# mini-midi-merge.net
KiCad netlist of a schematic drawn in EAGLE
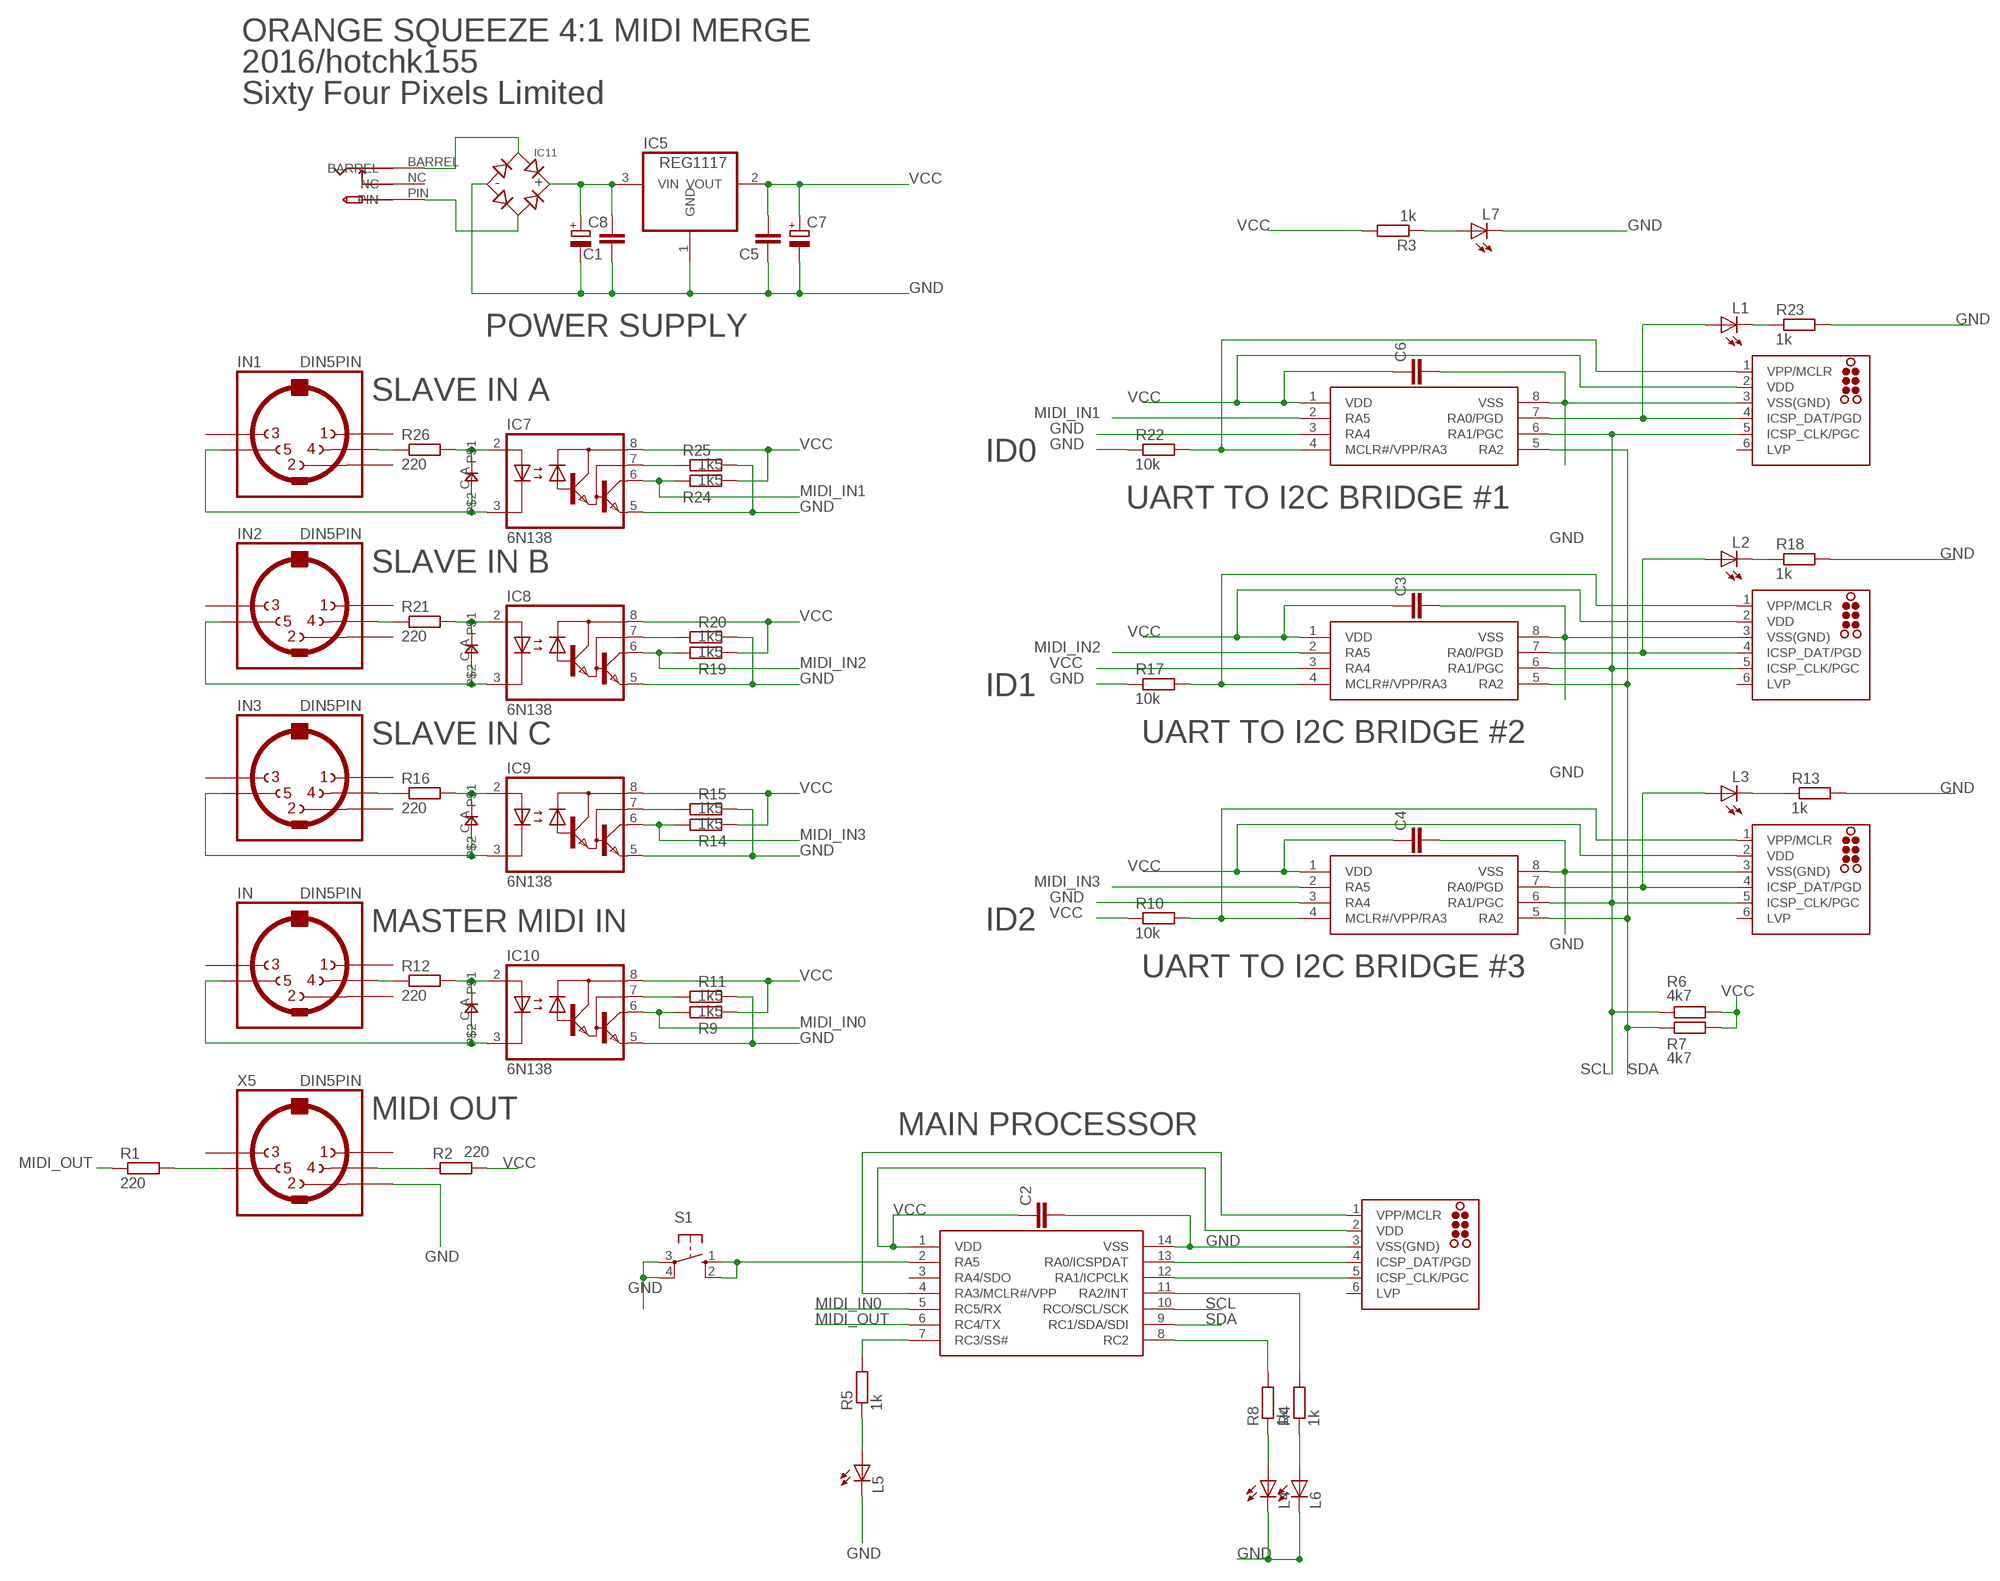
[diagram p0: schematic, sheet 1]

(export (version "E")
  (design (tool "Eeschema 10.0.6"))
  (components
    (comp (ref "C1")
      (value "C-EUC0805")
      (footprint "eagle-import:C0805")
      (libsource (lib "eagle-import") (part "C-EUC0805"))
    )
    (comp (ref "C2")
      (value "C-EUC0805")
      (footprint "eagle-import:C0805")
      (libsource (lib "eagle-import") (part "C-EUC0805"))
    )
    (comp (ref "C3")
      (value "C-EUC0805")
      (footprint "eagle-import:C0805")
      (libsource (lib "eagle-import") (part "C-EUC0805"))
    )
    (comp (ref "C4")
      (value "C-EUC0805")
      (footprint "eagle-import:C0805")
      (libsource (lib "eagle-import") (part "C-EUC0805"))
    )
    (comp (ref "C5")
      (value "C-EUC0805")
      (footprint "eagle-import:C0805")
      (libsource (lib "eagle-import") (part "C-EUC0805"))
    )
    (comp (ref "C6")
      (value "C-EUC0805")
      (footprint "eagle-import:C0805")
      (libsource (lib "eagle-import") (part "C-EUC0805"))
    )
    (comp (ref "C7")
      (value "CPOL-EUE2,5-6E")
      (footprint "eagle-import:E2,5-6E")
      (libsource (lib "eagle-import") (part "CPOL-EUE2,5-6E"))
    )
    (comp (ref "C8")
      (value "CPOL-EUE2,5-6E")
      (footprint "eagle-import:E2,5-6E")
      (libsource (lib "eagle-import") (part "CPOL-EUE2,5-6E"))
    )
    (comp (ref "D1")
      (value "0805DIODE")
      (footprint "eagle-import:0805DIODE")
      (libsource (lib "eagle-import") (part "0805DIODE"))
    )
    (comp (ref "D2")
      (value "0805DIODE")
      (footprint "eagle-import:0805DIODE")
      (libsource (lib "eagle-import") (part "0805DIODE"))
    )
    (comp (ref "D3")
      (value "0805DIODE")
      (footprint "eagle-import:0805DIODE")
      (libsource (lib "eagle-import") (part "0805DIODE"))
    )
    (comp (ref "D4")
      (value "0805DIODE")
      (footprint "eagle-import:0805DIODE")
      (libsource (lib "eagle-import") (part "0805DIODE"))
    )
    (comp (ref "IC1")
      (value "PIC16F1825SO14")
      (footprint "eagle-import:SO14")
      (libsource (lib "eagle-import") (part "PIC16F1825SO14"))
    )
    (comp (ref "IC2")
      (value "PIC12F1822SO08")
      (footprint "eagle-import:SO08")
      (libsource (lib "eagle-import") (part "PIC12F1822SO08"))
    )
    (comp (ref "IC3")
      (value "PIC12F1822SO08")
      (footprint "eagle-import:SO08")
      (libsource (lib "eagle-import") (part "PIC12F1822SO08"))
    )
    (comp (ref "IC4")
      (value "PIC12F1822SO08")
      (footprint "eagle-import:SO08")
      (libsource (lib "eagle-import") (part "PIC12F1822SO08"))
    )
    (comp (ref "IC5")
      (value "REG1117")
      (footprint "eagle-import:SOT223")
      (libsource (lib "eagle-import") (part "REG1117"))
    )
    (comp (ref "IC7")
      (value "6N138")
      (footprint "eagle-import:DIL08")
      (fields (field (name "MF") "VISHAY/TELEFUNKEN"))
      (libsource (lib "eagle-import") (part "6N138"))
    )
    (comp (ref "IC8")
      (value "6N138")
      (footprint "eagle-import:DIL08")
      (fields (field (name "MF") "VISHAY/TELEFUNKEN"))
      (libsource (lib "eagle-import") (part "6N138"))
    )
    (comp (ref "IC9")
      (value "6N138")
      (footprint "eagle-import:DIL08")
      (fields (field (name "MF") "VISHAY/TELEFUNKEN"))
      (libsource (lib "eagle-import") (part "6N138"))
    )
    (comp (ref "IC10")
      (value "6N138")
      (footprint "eagle-import:DIL08")
      (fields (field (name "MF") "VISHAY/TELEFUNKEN"))
      (libsource (lib "eagle-import") (part "6N138"))
    )
    (comp (ref "IC11")
      (value "BRIDGERECTIFIER")
      (footprint "eagle-import:SOIC-4")
      (libsource (lib "eagle-import") (part "BRIDGERECTIFIER"))
    )
    (comp (ref "ICSP1")
      (value "TC2030-MCP-NL")
      (footprint "eagle-import:TC2030-MCP-NL")
      (libsource (lib "eagle-import") (part "TC2030-MCP-NL"))
    )
    (comp (ref "ICSP2")
      (value "TC2030-MCP-NL")
      (footprint "eagle-import:TC2030-MCP-NL")
      (libsource (lib "eagle-import") (part "TC2030-MCP-NL"))
    )
    (comp (ref "ICSP3")
      (value "TC2030-MCP-NL")
      (footprint "eagle-import:TC2030-MCP-NL")
      (libsource (lib "eagle-import") (part "TC2030-MCP-NL"))
    )
    (comp (ref "ICSP4")
      (value "TC2030-MCP-NL")
      (footprint "eagle-import:TC2030-MCP-NL")
      (libsource (lib "eagle-import") (part "TC2030-MCP-NL"))
    )
    (comp (ref "IN")
      (value "DIN5PIN")
      (footprint "eagle-import:EDGEDIN")
      (libsource (lib "eagle-import") (part "DIN5PIN"))
    )
    (comp (ref "IN1")
      (value "DIN5PIN")
      (footprint "eagle-import:EDGEDIN")
      (libsource (lib "eagle-import") (part "DIN5PIN"))
    )
    (comp (ref "IN2")
      (value "DIN5PIN")
      (footprint "eagle-import:EDGEDIN")
      (libsource (lib "eagle-import") (part "DIN5PIN"))
    )
    (comp (ref "IN3")
      (value "DIN5PIN")
      (footprint "eagle-import:EDGEDIN")
      (libsource (lib "eagle-import") (part "DIN5PIN"))
    )
    (comp (ref "L1")
      (value "LED3MM")
      (footprint "eagle-import:LED3MM")
      (libsource (lib "eagle-import") (part "LED3MM"))
    )
    (comp (ref "L2")
      (value "LED3MM")
      (footprint "eagle-import:LED3MM")
      (libsource (lib "eagle-import") (part "LED3MM"))
    )
    (comp (ref "L3")
      (value "LED3MM")
      (footprint "eagle-import:LED3MM")
      (libsource (lib "eagle-import") (part "LED3MM"))
    )
    (comp (ref "L4")
      (value "LED3MM")
      (footprint "eagle-import:LED3MM")
      (libsource (lib "eagle-import") (part "LED3MM"))
    )
    (comp (ref "L5")
      (value "LED3MM")
      (footprint "eagle-import:LED3MM")
      (libsource (lib "eagle-import") (part "LED3MM"))
    )
    (comp (ref "L6")
      (value "LED3MM")
      (footprint "eagle-import:LED3MM")
      (libsource (lib "eagle-import") (part "LED3MM"))
    )
    (comp (ref "L7")
      (value "LED3MM")
      (footprint "eagle-import:LED3MM")
      (libsource (lib "eagle-import") (part "LED3MM"))
    )
    (comp (ref "R1")
      (value "220")
      (footprint "eagle-import:R0805")
      (libsource (lib "eagle-import") (part "R-EU_R0805"))
    )
    (comp (ref "R2")
      (value "220")
      (footprint "eagle-import:R0805")
      (libsource (lib "eagle-import") (part "R-EU_R0805"))
    )
    (comp (ref "R3")
      (value "1k")
      (footprint "eagle-import:R0805")
      (libsource (lib "eagle-import") (part "R-EU_R0805"))
    )
    (comp (ref "R4")
      (value "1k")
      (footprint "eagle-import:R0805")
      (libsource (lib "eagle-import") (part "R-EU_R0805"))
    )
    (comp (ref "R5")
      (value "1k")
      (footprint "eagle-import:R0805")
      (libsource (lib "eagle-import") (part "R-EU_R0805"))
    )
    (comp (ref "R6")
      (value "4k7")
      (footprint "eagle-import:R0805")
      (libsource (lib "eagle-import") (part "R-EU_R0805"))
    )
    (comp (ref "R7")
      (value "4k7")
      (footprint "eagle-import:R0805")
      (libsource (lib "eagle-import") (part "R-EU_R0805"))
    )
    (comp (ref "R8")
      (value "1k")
      (footprint "eagle-import:R0805")
      (libsource (lib "eagle-import") (part "R-EU_R0805"))
    )
    (comp (ref "R9")
      (value "1k5")
      (footprint "eagle-import:R0805")
      (libsource (lib "eagle-import") (part "R-EU_R0805"))
    )
    (comp (ref "R10")
      (value "10k")
      (footprint "eagle-import:R0805")
      (libsource (lib "eagle-import") (part "R-EU_R0805"))
    )
    (comp (ref "R11")
      (value "1k5")
      (footprint "eagle-import:R0805")
      (libsource (lib "eagle-import") (part "R-EU_R0805"))
    )
    (comp (ref "R12")
      (value "220")
      (footprint "eagle-import:R0805")
      (libsource (lib "eagle-import") (part "R-EU_R0805"))
    )
    (comp (ref "R13")
      (value "1k")
      (footprint "eagle-import:R0805")
      (libsource (lib "eagle-import") (part "R-EU_R0805"))
    )
    (comp (ref "R14")
      (value "1k5")
      (footprint "eagle-import:R0805")
      (libsource (lib "eagle-import") (part "R-EU_R0805"))
    )
    (comp (ref "R15")
      (value "1k5")
      (footprint "eagle-import:R0805")
      (libsource (lib "eagle-import") (part "R-EU_R0805"))
    )
    (comp (ref "R16")
      (value "220")
      (footprint "eagle-import:R0805")
      (libsource (lib "eagle-import") (part "R-EU_R0805"))
    )
    (comp (ref "R17")
      (value "10k")
      (footprint "eagle-import:R0805")
      (libsource (lib "eagle-import") (part "R-EU_R0805"))
    )
    (comp (ref "R18")
      (value "1k")
      (footprint "eagle-import:R0805")
      (libsource (lib "eagle-import") (part "R-EU_R0805"))
    )
    (comp (ref "R19")
      (value "1k5")
      (footprint "eagle-import:R0805")
      (libsource (lib "eagle-import") (part "R-EU_R0805"))
    )
    (comp (ref "R20")
      (value "1k5")
      (footprint "eagle-import:R0805")
      (libsource (lib "eagle-import") (part "R-EU_R0805"))
    )
    (comp (ref "R21")
      (value "220")
      (footprint "eagle-import:R0805")
      (libsource (lib "eagle-import") (part "R-EU_R0805"))
    )
    (comp (ref "R22")
      (value "10k")
      (footprint "eagle-import:R0805")
      (libsource (lib "eagle-import") (part "R-EU_R0805"))
    )
    (comp (ref "R23")
      (value "1k")
      (footprint "eagle-import:R0805")
      (libsource (lib "eagle-import") (part "R-EU_R0805"))
    )
    (comp (ref "R24")
      (value "1k5")
      (footprint "eagle-import:R0805")
      (libsource (lib "eagle-import") (part "R-EU_R0805"))
    )
    (comp (ref "R25")
      (value "1k5")
      (footprint "eagle-import:R0805")
      (libsource (lib "eagle-import") (part "R-EU_R0805"))
    )
    (comp (ref "R26")
      (value "220")
      (footprint "eagle-import:R0805")
      (libsource (lib "eagle-import") (part "R-EU_R0805"))
    )
    (comp (ref "S1")
      (value "10-XX")
      (footprint "eagle-import:B3F-10XX")
      (fields (field (name "MPN") "B3F-1000"))
      (libsource (lib "eagle-import") (part "10-XX"))
    )
    (comp (ref "U$9")
      (value "PWR_SOCKET_2_1MM")
      (footprint "eagle-import:PWR_SOCKET_2_1MM")
      (libsource (lib "eagle-import") (part "PWR_SOCKET_2_1MM"))
    )
    (comp (ref "X5")
      (value "DIN5PIN")
      (footprint "eagle-import:EDGEDIN")
      (libsource (lib "eagle-import") (part "DIN5PIN"))
    )
  )
  (nets
    (net (code "1") (name "/GND") (class "Default")
      (node (ref "C1") (pin "1") (pinfunction "1_1") (pintype "passive"))
      (node (ref "C2") (pin "2") (pinfunction "2_2") (pintype "passive"))
      (node (ref "C3") (pin "2") (pinfunction "2_2") (pintype "passive"))
      (node (ref "C4") (pin "2") (pinfunction "2_2") (pintype "passive"))
      (node (ref "C5") (pin "1") (pinfunction "1_1") (pintype "passive"))
      (node (ref "C6") (pin "2") (pinfunction "2_2") (pintype "passive"))
      (node (ref "C7") (pin "-") (pinfunction "-_-") (pintype "passive"))
      (node (ref "C8") (pin "-") (pinfunction "-_-") (pintype "passive"))
      (node (ref "IC1") (pin "14") (pinfunction "VSS_14") (pintype "power_in"))
      (node (ref "IC10") (pin "5") (pinfunction "GND_5") (pintype "passive"))
      (node (ref "IC11") (pin "-") (pinfunction "-_-") (pintype "passive"))
      (node (ref "IC2") (pin "3") (pinfunction "RA4_3") (pintype "bidirectional"))
      (node (ref "IC2") (pin "8") (pinfunction "VSS_8") (pintype "power_in"))
      (node (ref "IC3") (pin "8") (pinfunction "VSS_8") (pintype "power_in"))
      (node (ref "IC4") (pin "3") (pinfunction "RA4_3") (pintype "bidirectional"))
      (node (ref "IC4") (pin "8") (pinfunction "VSS_8") (pintype "power_in"))
      (node (ref "IC5") (pin "1") (pinfunction "GND_1") (pintype "power_in"))
      (node (ref "IC7") (pin "5") (pinfunction "GND_5") (pintype "passive"))
      (node (ref "IC8") (pin "5") (pinfunction "GND_5") (pintype "passive"))
      (node (ref "IC9") (pin "5") (pinfunction "GND_5") (pintype "passive"))
      (node (ref "ICSP1") (pin "3") (pinfunction "VSS(GND)_3") (pintype "power_in"))
      (node (ref "ICSP2") (pin "3") (pinfunction "VSS(GND)_3") (pintype "power_in"))
      (node (ref "ICSP3") (pin "3") (pinfunction "VSS(GND)_3") (pintype "power_in"))
      (node (ref "ICSP4") (pin "3") (pinfunction "VSS(GND)_3") (pintype "power_in"))
      (node (ref "L4") (pin "K") (pinfunction "C_K") (pintype "passive"))
      (node (ref "L5") (pin "K") (pinfunction "C_K") (pintype "passive"))
      (node (ref "L6") (pin "K") (pinfunction "C_K") (pintype "passive"))
      (node (ref "L7") (pin "K") (pinfunction "C_K") (pintype "passive"))
      (node (ref "R11") (pin "2") (pinfunction "2_2") (pintype "passive"))
      (node (ref "R13") (pin "2") (pinfunction "2_2") (pintype "passive"))
      (node (ref "R15") (pin "2") (pinfunction "2_2") (pintype "passive"))
      (node (ref "R17") (pin "1") (pinfunction "1_1") (pintype "passive"))
      (node (ref "R18") (pin "2") (pinfunction "2_2") (pintype "passive"))
      (node (ref "R20") (pin "2") (pinfunction "2_2") (pintype "passive"))
      (node (ref "R22") (pin "1") (pinfunction "1_1") (pintype "passive"))
      (node (ref "R23") (pin "2") (pinfunction "2_2") (pintype "passive"))
      (node (ref "R25") (pin "2") (pinfunction "2_2") (pintype "passive"))
      (node (ref "S1") (pin "3") (pinfunction "P_3") (pintype "passive"))
      (node (ref "S1") (pin "4") (pinfunction "P1_4") (pintype "passive"))
      (node (ref "X5") (pin "2") (pinfunction "2_2") (pintype "passive"))
    )
    (net (code "2") (name "/MIDI_IN0") (class "Default")
      (node (ref "IC1") (pin "5") (pinfunction "RC5/RX_5") (pintype "bidirectional"))
      (node (ref "IC10") (pin "6") (pinfunction "VO_6") (pintype "passive"))
      (node (ref "R9") (pin "1") (pinfunction "1_1") (pintype "passive"))
    )
    (net (code "3") (name "/MIDI_IN1") (class "Default")
      (node (ref "IC4") (pin "2") (pinfunction "RA5_2") (pintype "bidirectional"))
      (node (ref "IC7") (pin "6") (pinfunction "VO_6") (pintype "passive"))
      (node (ref "R24") (pin "1") (pinfunction "1_1") (pintype "passive"))
    )
    (net (code "4") (name "/MIDI_IN2") (class "Default")
      (node (ref "IC3") (pin "2") (pinfunction "RA5_2") (pintype "bidirectional"))
      (node (ref "IC8") (pin "6") (pinfunction "VO_6") (pintype "passive"))
      (node (ref "R19") (pin "1") (pinfunction "1_1") (pintype "passive"))
    )
    (net (code "5") (name "/MIDI_IN3") (class "Default")
      (node (ref "IC2") (pin "2") (pinfunction "RA5_2") (pintype "bidirectional"))
      (node (ref "IC9") (pin "6") (pinfunction "VO_6") (pintype "passive"))
      (node (ref "R14") (pin "1") (pinfunction "1_1") (pintype "passive"))
    )
    (net (code "6") (name "/MIDI_OUT") (class "Default")
      (node (ref "IC1") (pin "6") (pinfunction "RC4/TX_6") (pintype "bidirectional"))
      (node (ref "R1") (pin "1") (pinfunction "1_1") (pintype "passive"))
    )
    (net (code "7") (name "/SCL") (class "Default")
      (node (ref "IC1") (pin "10") (pinfunction "RCO/SCL/SCK_10") (pintype "bidirectional"))
      (node (ref "IC2") (pin "6") (pinfunction "RA1/PGC_6") (pintype "bidirectional"))
      (node (ref "IC3") (pin "6") (pinfunction "RA1/PGC_6") (pintype "bidirectional"))
      (node (ref "IC4") (pin "6") (pinfunction "RA1/PGC_6") (pintype "bidirectional"))
      (node (ref "ICSP2") (pin "5") (pinfunction "ICSP_CLK/PGC_5") (pintype "output"))
      (node (ref "ICSP3") (pin "5") (pinfunction "ICSP_CLK/PGC_5") (pintype "output"))
      (node (ref "ICSP4") (pin "5") (pinfunction "ICSP_CLK/PGC_5") (pintype "output"))
      (node (ref "R6") (pin "1") (pinfunction "1_1") (pintype "passive"))
    )
    (net (code "8") (name "/SDA") (class "Default")
      (node (ref "IC1") (pin "9") (pinfunction "RC1/SDA/SDI_9") (pintype "bidirectional"))
      (node (ref "IC2") (pin "5") (pinfunction "RA2_5") (pintype "bidirectional"))
      (node (ref "IC3") (pin "5") (pinfunction "RA2_5") (pintype "bidirectional"))
      (node (ref "IC4") (pin "5") (pinfunction "RA2_5") (pintype "bidirectional"))
      (node (ref "R7") (pin "1") (pinfunction "1_1") (pintype "passive"))
    )
    (net (code "9") (name "/VCC") (class "Default")
      (node (ref "C2") (pin "1") (pinfunction "1_1") (pintype "passive"))
      (node (ref "C3") (pin "1") (pinfunction "1_1") (pintype "passive"))
      (node (ref "C4") (pin "1") (pinfunction "1_1") (pintype "passive"))
      (node (ref "C5") (pin "2") (pinfunction "2_2") (pintype "passive"))
      (node (ref "C6") (pin "1") (pinfunction "1_1") (pintype "passive"))
      (node (ref "C7") (pin "+") (pinfunction "+_+") (pintype "passive"))
      (node (ref "IC1") (pin "1") (pinfunction "VDD_1") (pintype "power_in"))
      (node (ref "IC10") (pin "8") (pinfunction "VCC_8") (pintype "passive"))
      (node (ref "IC2") (pin "1") (pinfunction "VDD_1") (pintype "power_in"))
      (node (ref "IC3") (pin "1") (pinfunction "VDD_1") (pintype "power_in"))
      (node (ref "IC3") (pin "3") (pinfunction "RA4_3") (pintype "bidirectional"))
      (node (ref "IC4") (pin "1") (pinfunction "VDD_1") (pintype "power_in"))
      (node (ref "IC5") (pin "2") (pinfunction "VOUT_2") (pintype "output"))
      (node (ref "IC7") (pin "8") (pinfunction "VCC_8") (pintype "passive"))
      (node (ref "IC8") (pin "8") (pinfunction "VCC_8") (pintype "passive"))
      (node (ref "IC9") (pin "8") (pinfunction "VCC_8") (pintype "passive"))
      (node (ref "ICSP1") (pin "2") (pinfunction "VDD_2") (pintype "power_in"))
      (node (ref "ICSP2") (pin "2") (pinfunction "VDD_2") (pintype "power_in"))
      (node (ref "ICSP3") (pin "2") (pinfunction "VDD_2") (pintype "power_in"))
      (node (ref "ICSP4") (pin "2") (pinfunction "VDD_2") (pintype "power_in"))
      (node (ref "R10") (pin "1") (pinfunction "1_1") (pintype "passive"))
      (node (ref "R14") (pin "2") (pinfunction "2_2") (pintype "passive"))
      (node (ref "R19") (pin "2") (pinfunction "2_2") (pintype "passive"))
      (node (ref "R2") (pin "2") (pinfunction "2_2") (pintype "passive"))
      (node (ref "R24") (pin "2") (pinfunction "2_2") (pintype "passive"))
      (node (ref "R3") (pin "2") (pinfunction "2_2") (pintype "passive"))
      (node (ref "R6") (pin "2") (pinfunction "2_2") (pintype "passive"))
      (node (ref "R7") (pin "2") (pinfunction "2_2") (pintype "passive"))
      (node (ref "R9") (pin "2") (pinfunction "2_2") (pintype "passive"))
    )
    (net (code "10") (name "Net-(D1-P$1)") (class "Default")
      (node (ref "D1") (pin "C") (pinfunction "P$1_C") (pintype "bidirectional"))
      (node (ref "IC10") (pin "3") (pinfunction "C_3") (pintype "passive"))
      (node (ref "IN") (pin "5") (pinfunction "5_5") (pintype "passive"))
    )
    (net (code "11") (name "Net-(D1-P$2)") (class "Default")
      (node (ref "D1") (pin "A") (pinfunction "P$2_A") (pintype "bidirectional"))
      (node (ref "IC10") (pin "2") (pinfunction "A_2") (pintype "passive"))
      (node (ref "R12") (pin "2") (pinfunction "2_2") (pintype "passive"))
    )
    (net (code "12") (name "Net-(D2-P$1)") (class "Default")
      (node (ref "D2") (pin "C") (pinfunction "P$1_C") (pintype "bidirectional"))
      (node (ref "IC9") (pin "3") (pinfunction "C_3") (pintype "passive"))
      (node (ref "IN3") (pin "5") (pinfunction "5_5") (pintype "passive"))
    )
    (net (code "13") (name "Net-(D2-P$2)") (class "Default")
      (node (ref "D2") (pin "A") (pinfunction "P$2_A") (pintype "bidirectional"))
      (node (ref "IC9") (pin "2") (pinfunction "A_2") (pintype "passive"))
      (node (ref "R16") (pin "2") (pinfunction "2_2") (pintype "passive"))
    )
    (net (code "14") (name "Net-(D3-P$1)") (class "Default")
      (node (ref "D3") (pin "C") (pinfunction "P$1_C") (pintype "bidirectional"))
      (node (ref "IC8") (pin "3") (pinfunction "C_3") (pintype "passive"))
      (node (ref "IN2") (pin "5") (pinfunction "5_5") (pintype "passive"))
    )
    (net (code "15") (name "Net-(D3-P$2)") (class "Default")
      (node (ref "D3") (pin "A") (pinfunction "P$2_A") (pintype "bidirectional"))
      (node (ref "IC8") (pin "2") (pinfunction "A_2") (pintype "passive"))
      (node (ref "R21") (pin "2") (pinfunction "2_2") (pintype "passive"))
    )
    (net (code "16") (name "Net-(D4-P$1)") (class "Default")
      (node (ref "D4") (pin "C") (pinfunction "P$1_C") (pintype "bidirectional"))
      (node (ref "IC7") (pin "3") (pinfunction "C_3") (pintype "passive"))
      (node (ref "IN1") (pin "5") (pinfunction "5_5") (pintype "passive"))
    )
    (net (code "17") (name "Net-(D4-P$2)") (class "Default")
      (node (ref "D4") (pin "A") (pinfunction "P$2_A") (pintype "bidirectional"))
      (node (ref "IC7") (pin "2") (pinfunction "A_2") (pintype "passive"))
      (node (ref "R26") (pin "2") (pinfunction "2_2") (pintype "passive"))
    )
    (net (code "18") (name "Net-(IC1-RA0{slash}ICSPDAT)") (class "Default")
      (node (ref "IC1") (pin "13") (pinfunction "RA0/ICSPDAT_13") (pintype "bidirectional"))
      (node (ref "ICSP1") (pin "4") (pinfunction "ICSP_DAT/PGD_4") (pintype "bidirectional"))
    )
    (net (code "19") (name "Net-(IC1-RA1{slash}ICPCLK)") (class "Default")
      (node (ref "IC1") (pin "12") (pinfunction "RA1/ICPCLK_12") (pintype "bidirectional"))
      (node (ref "ICSP1") (pin "5") (pinfunction "ICSP_CLK/PGC_5") (pintype "output"))
    )
    (net (code "20") (name "Net-(IC1-RA2{slash}INT)") (class "Default")
      (node (ref "IC1") (pin "11") (pinfunction "RA2/INT_11") (pintype "bidirectional"))
      (node (ref "R4") (pin "2") (pinfunction "2_2") (pintype "passive"))
    )
    (net (code "21") (name "Net-(IC1-RA3{slash}MCLR#{slash}VPP)") (class "Default")
      (node (ref "IC1") (pin "4") (pinfunction "RA3/MCLR#/VPP_4") (pintype "input"))
      (node (ref "ICSP1") (pin "1") (pinfunction "VPP/MCLR_1") (pintype "passive"))
    )
    (net (code "22") (name "Net-(IC1-RA5)") (class "Default")
      (node (ref "IC1") (pin "2") (pinfunction "RA5_2") (pintype "bidirectional"))
      (node (ref "S1") (pin "1") (pinfunction "S_1") (pintype "passive"))
      (node (ref "S1") (pin "2") (pinfunction "S1_2") (pintype "passive"))
    )
    (net (code "23") (name "Net-(IC1-RC2)") (class "Default")
      (node (ref "IC1") (pin "8") (pinfunction "RC2_8") (pintype "bidirectional"))
      (node (ref "R8") (pin "2") (pinfunction "2_2") (pintype "passive"))
    )
    (net (code "24") (name "Net-(IC1-RC3{slash}SS#)") (class "Default")
      (node (ref "IC1") (pin "7") (pinfunction "RC3/SS#_7") (pintype "bidirectional"))
      (node (ref "R5") (pin "2") (pinfunction "2_2") (pintype "passive"))
    )
    (net (code "25") (name "Net-(IC2-MCLR#{slash}VPP{slash}RA3)") (class "Default")
      (node (ref "IC2") (pin "4") (pinfunction "MCLR#/VPP/RA3_4") (pintype "bidirectional"))
      (node (ref "ICSP2") (pin "1") (pinfunction "VPP/MCLR_1") (pintype "passive"))
      (node (ref "R10") (pin "2") (pinfunction "2_2") (pintype "passive"))
    )
    (net (code "26") (name "Net-(IC2-RA0{slash}PGD)") (class "Default")
      (node (ref "IC2") (pin "7") (pinfunction "RA0/PGD_7") (pintype "bidirectional"))
      (node (ref "ICSP2") (pin "4") (pinfunction "ICSP_DAT/PGD_4") (pintype "bidirectional"))
      (node (ref "L3") (pin "A") (pinfunction "A_A") (pintype "passive"))
    )
    (net (code "27") (name "Net-(IC3-MCLR#{slash}VPP{slash}RA3)") (class "Default")
      (node (ref "IC3") (pin "4") (pinfunction "MCLR#/VPP/RA3_4") (pintype "bidirectional"))
      (node (ref "ICSP3") (pin "1") (pinfunction "VPP/MCLR_1") (pintype "passive"))
      (node (ref "R17") (pin "2") (pinfunction "2_2") (pintype "passive"))
    )
    (net (code "28") (name "Net-(IC3-RA0{slash}PGD)") (class "Default")
      (node (ref "IC3") (pin "7") (pinfunction "RA0/PGD_7") (pintype "bidirectional"))
      (node (ref "ICSP3") (pin "4") (pinfunction "ICSP_DAT/PGD_4") (pintype "bidirectional"))
      (node (ref "L2") (pin "A") (pinfunction "A_A") (pintype "passive"))
    )
    (net (code "29") (name "Net-(IC4-MCLR#{slash}VPP{slash}RA3)") (class "Default")
      (node (ref "IC4") (pin "4") (pinfunction "MCLR#/VPP/RA3_4") (pintype "bidirectional"))
      (node (ref "ICSP4") (pin "1") (pinfunction "VPP/MCLR_1") (pintype "passive"))
      (node (ref "R22") (pin "2") (pinfunction "2_2") (pintype "passive"))
    )
    (net (code "30") (name "Net-(IC4-RA0{slash}PGD)") (class "Default")
      (node (ref "IC4") (pin "7") (pinfunction "RA0/PGD_7") (pintype "bidirectional"))
      (node (ref "ICSP4") (pin "4") (pinfunction "ICSP_DAT/PGD_4") (pintype "bidirectional"))
      (node (ref "L1") (pin "A") (pinfunction "A_A") (pintype "passive"))
    )
    (net (code "31") (name "Net-(IC5-VIN)") (class "Default")
      (node (ref "C1") (pin "2") (pinfunction "2_2") (pintype "passive"))
      (node (ref "C8") (pin "+") (pinfunction "+_+") (pintype "passive"))
      (node (ref "IC11") (pin "+") (pinfunction "+_+") (pintype "passive"))
      (node (ref "IC5") (pin "3") (pinfunction "VIN_3") (pintype "input"))
    )
    (net (code "32") (name "Net-(IC7-VB)") (class "Default")
      (node (ref "IC7") (pin "7") (pinfunction "VB_7") (pintype "passive"))
      (node (ref "R25") (pin "1") (pinfunction "1_1") (pintype "passive"))
    )
    (net (code "33") (name "Net-(IC8-VB)") (class "Default")
      (node (ref "IC8") (pin "7") (pinfunction "VB_7") (pintype "passive"))
      (node (ref "R20") (pin "1") (pinfunction "1_1") (pintype "passive"))
    )
    (net (code "34") (name "Net-(IC9-VB)") (class "Default")
      (node (ref "IC9") (pin "7") (pinfunction "VB_7") (pintype "passive"))
      (node (ref "R15") (pin "1") (pinfunction "1_1") (pintype "passive"))
    )
    (net (code "35") (name "Net-(IC10-VB)") (class "Default")
      (node (ref "IC10") (pin "7") (pinfunction "VB_7") (pintype "passive"))
      (node (ref "R11") (pin "1") (pinfunction "1_1") (pintype "passive"))
    )
    (net (code "36") (name "Net-(IC11-AC1)") (class "Default")
      (node (ref "IC11") (pin "~1") (pinfunction "AC1_~1") (pintype "passive"))
      (node (ref "U$9") (pin "BARREL") (pinfunction "BARREL_BARREL") (pintype "bidirectional"))
    )
    (net (code "37") (name "Net-(IC11-AC2)") (class "Default")
      (node (ref "IC11") (pin "~2") (pinfunction "AC2_~2") (pintype "passive"))
      (node (ref "U$9") (pin "PIN") (pinfunction "PIN_PIN") (pintype "bidirectional"))
    )
    (net (code "38") (name "Net-(IN-Pad4)") (class "Default")
      (node (ref "IN") (pin "4") (pinfunction "4_4") (pintype "passive"))
      (node (ref "R12") (pin "1") (pinfunction "1_1") (pintype "passive"))
    )
    (net (code "39") (name "Net-(IN1-Pad4)") (class "Default")
      (node (ref "IN1") (pin "4") (pinfunction "4_4") (pintype "passive"))
      (node (ref "R26") (pin "1") (pinfunction "1_1") (pintype "passive"))
    )
    (net (code "40") (name "Net-(IN2-Pad4)") (class "Default")
      (node (ref "IN2") (pin "4") (pinfunction "4_4") (pintype "passive"))
      (node (ref "R21") (pin "1") (pinfunction "1_1") (pintype "passive"))
    )
    (net (code "41") (name "Net-(IN3-Pad4)") (class "Default")
      (node (ref "IN3") (pin "4") (pinfunction "4_4") (pintype "passive"))
      (node (ref "R16") (pin "1") (pinfunction "1_1") (pintype "passive"))
    )
    (net (code "42") (name "Net-(L1-C)") (class "Default")
      (node (ref "L1") (pin "K") (pinfunction "C_K") (pintype "passive"))
      (node (ref "R23") (pin "1") (pinfunction "1_1") (pintype "passive"))
    )
    (net (code "43") (name "Net-(L2-C)") (class "Default")
      (node (ref "L2") (pin "K") (pinfunction "C_K") (pintype "passive"))
      (node (ref "R18") (pin "1") (pinfunction "1_1") (pintype "passive"))
    )
    (net (code "44") (name "Net-(L3-C)") (class "Default")
      (node (ref "L3") (pin "K") (pinfunction "C_K") (pintype "passive"))
      (node (ref "R13") (pin "1") (pinfunction "1_1") (pintype "passive"))
    )
    (net (code "45") (name "Net-(L4-PadA)") (class "Default")
      (node (ref "L4") (pin "A") (pinfunction "A_A") (pintype "passive"))
      (node (ref "R8") (pin "1") (pinfunction "1_1") (pintype "passive"))
    )
    (net (code "46") (name "Net-(L5-PadA)") (class "Default")
      (node (ref "L5") (pin "A") (pinfunction "A_A") (pintype "passive"))
      (node (ref "R5") (pin "1") (pinfunction "1_1") (pintype "passive"))
    )
    (net (code "47") (name "Net-(L6-PadA)") (class "Default")
      (node (ref "L6") (pin "A") (pinfunction "A_A") (pintype "passive"))
      (node (ref "R4") (pin "1") (pinfunction "1_1") (pintype "passive"))
    )
    (net (code "48") (name "Net-(L7-PadA)") (class "Default")
      (node (ref "L7") (pin "A") (pinfunction "A_A") (pintype "passive"))
      (node (ref "R3") (pin "1") (pinfunction "1_1") (pintype "passive"))
    )
    (net (code "49") (name "Net-(R1-Pad2)") (class "Default")
      (node (ref "R1") (pin "2") (pinfunction "2_2") (pintype "passive"))
      (node (ref "X5") (pin "5") (pinfunction "5_5") (pintype "passive"))
    )
    (net (code "50") (name "Net-(R2-Pad1)") (class "Default")
      (node (ref "R2") (pin "1") (pinfunction "1_1") (pintype "passive"))
      (node (ref "X5") (pin "4") (pinfunction "4_4") (pintype "passive"))
    )
    (net (code "51") (name "unconnected-(IC1-RA4{slash}SDO-Pad3)") (class "Default")
      (node (ref "IC1") (pin "3") (pinfunction "RA4/SDO_3") (pintype "bidirectional"))
    )
    (net (code "52") (name "unconnected-(ICSP1-LVP-Pad6)") (class "Default")
      (node (ref "ICSP1") (pin "6") (pinfunction "LVP_6") (pintype "bidirectional"))
    )
    (net (code "53") (name "unconnected-(ICSP2-LVP-Pad6)") (class "Default")
      (node (ref "ICSP2") (pin "6") (pinfunction "LVP_6") (pintype "bidirectional"))
    )
    (net (code "54") (name "unconnected-(ICSP3-LVP-Pad6)") (class "Default")
      (node (ref "ICSP3") (pin "6") (pinfunction "LVP_6") (pintype "bidirectional"))
    )
    (net (code "55") (name "unconnected-(ICSP4-LVP-Pad6)") (class "Default")
      (node (ref "ICSP4") (pin "6") (pinfunction "LVP_6") (pintype "bidirectional"))
    )
    (net (code "56") (name "unconnected-(IN-Pad1)") (class "Default")
      (node (ref "IN") (pin "1") (pinfunction "1_1") (pintype "passive"))
    )
    (net (code "57") (name "unconnected-(IN-Pad2)") (class "Default")
      (node (ref "IN") (pin "2") (pinfunction "2_2") (pintype "passive"))
    )
    (net (code "58") (name "unconnected-(IN-Pad3)") (class "Default")
      (node (ref "IN") (pin "3") (pinfunction "3_3") (pintype "passive"))
    )
    (net (code "59") (name "unconnected-(IN1-Pad1)") (class "Default")
      (node (ref "IN1") (pin "1") (pinfunction "1_1") (pintype "passive"))
    )
    (net (code "60") (name "unconnected-(IN1-Pad2)") (class "Default")
      (node (ref "IN1") (pin "2") (pinfunction "2_2") (pintype "passive"))
    )
    (net (code "61") (name "unconnected-(IN1-Pad3)") (class "Default")
      (node (ref "IN1") (pin "3") (pinfunction "3_3") (pintype "passive"))
    )
    (net (code "62") (name "unconnected-(IN2-Pad1)") (class "Default")
      (node (ref "IN2") (pin "1") (pinfunction "1_1") (pintype "passive"))
    )
    (net (code "63") (name "unconnected-(IN2-Pad2)") (class "Default")
      (node (ref "IN2") (pin "2") (pinfunction "2_2") (pintype "passive"))
    )
    (net (code "64") (name "unconnected-(IN2-Pad3)") (class "Default")
      (node (ref "IN2") (pin "3") (pinfunction "3_3") (pintype "passive"))
    )
    (net (code "65") (name "unconnected-(IN3-Pad1)") (class "Default")
      (node (ref "IN3") (pin "1") (pinfunction "1_1") (pintype "passive"))
    )
    (net (code "66") (name "unconnected-(IN3-Pad2)") (class "Default")
      (node (ref "IN3") (pin "2") (pinfunction "2_2") (pintype "passive"))
    )
    (net (code "67") (name "unconnected-(IN3-Pad3)") (class "Default")
      (node (ref "IN3") (pin "3") (pinfunction "3_3") (pintype "passive"))
    )
    (net (code "68") (name "unconnected-(U$9-PadNC)") (class "Default")
      (node (ref "U$9") (pin "NC") (pinfunction "NC_NC") (pintype "bidirectional"))
    )
    (net (code "69") (name "unconnected-(X5-Pad1)") (class "Default")
      (node (ref "X5") (pin "1") (pinfunction "1_1") (pintype "passive"))
    )
    (net (code "70") (name "unconnected-(X5-Pad3)") (class "Default")
      (node (ref "X5") (pin "3") (pinfunction "3_3") (pintype "passive"))
    )
  )
)
